# 44_pin_BB.net
KiCad netlist of a schematic drawn in EAGLE
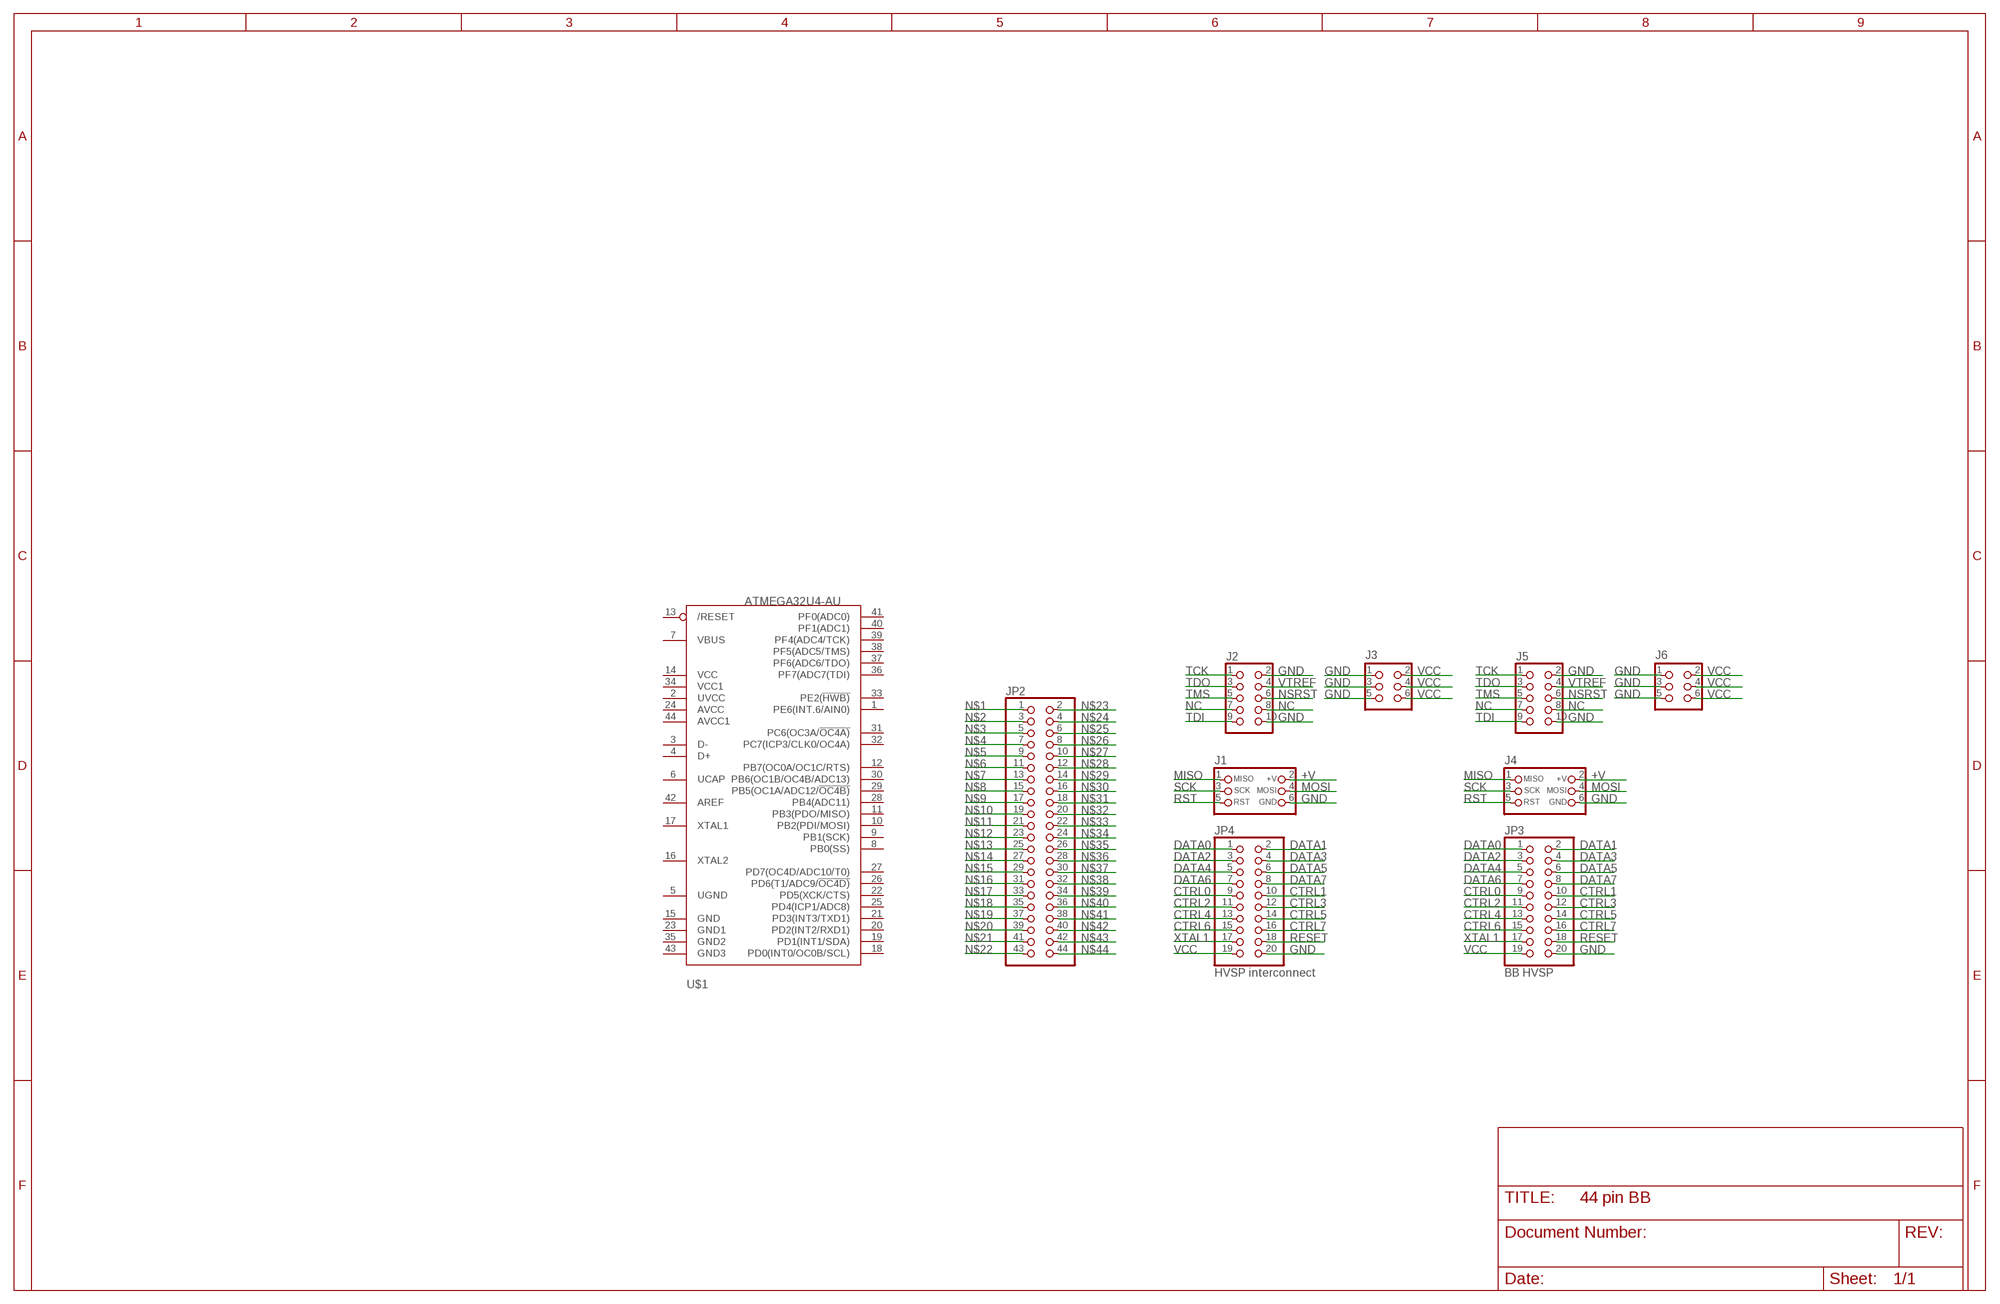
[diagram p0: schematic, sheet 1]

(export (version "E")
  (design (tool "Eeschema 10.0.6"))
  (components
    (comp (ref "J1")
      (value "CON_HEADER_PRG_AVR_ICSP")
      (footprint "eagle-import:HEADER_PRG_2X03")
      (libsource (lib "eagle-import") (part "CON_HEADER_PRG_AVR_ICSP"))
    )
    (comp (ref "J2")
      (value "CON_HEADER_2X05-PTH")
      (footprint "eagle-import:M2X5")
      (libsource (lib "eagle-import") (part "CON_HEADER_2X05-PTH"))
    )
    (comp (ref "J3")
      (value "CON_HEADER_2X03-PTH")
      (footprint "eagle-import:M2X3")
      (libsource (lib "eagle-import") (part "CON_HEADER_2X03-PTH"))
    )
    (comp (ref "J4")
      (value "CON_HEADER_PRG_AVR_ICSP")
      (footprint "eagle-import:HEADER_PRG_2X03")
      (libsource (lib "eagle-import") (part "CON_HEADER_PRG_AVR_ICSP"))
    )
    (comp (ref "J5")
      (value "CON_HEADER_2X05-PTH")
      (footprint "eagle-import:M2X5")
      (libsource (lib "eagle-import") (part "CON_HEADER_2X05-PTH"))
    )
    (comp (ref "J6")
      (value "CON_HEADER_2X03-PTH")
      (footprint "eagle-import:M2X3")
      (libsource (lib "eagle-import") (part "CON_HEADER_2X03-PTH"))
    )
    (comp (ref "JP2")
      (value "PINHD-2X22")
      (footprint "eagle-import:2X22")
      (libsource (lib "eagle-import") (part "PINHD-2X22"))
    )
    (comp (ref "JP3")
      (value "BB HVSP")
      (footprint "eagle-import:2X10")
      (libsource (lib "eagle-import") (part "PINHD-2X10"))
    )
    (comp (ref "JP4")
      (value "HVSP interconnect")
      (footprint "eagle-import:2X10")
      (libsource (lib "eagle-import") (part "PINHD-2X10"))
    )
    (comp (ref "U$1")
      (value "ATMEGA32U4-AU")
      (footprint "eagle-import:TQFP44")
      (libsource (lib "eagle-import") (part "ATMEGA32U4-AU"))
    )
  )
  (nets
    (net (code "1") (name "/+V") (class "Default")
      (node (ref "J1") (pin "2") (pinfunction "+V_2") (pintype "passive"))
      (node (ref "J4") (pin "2") (pinfunction "+V_2") (pintype "passive"))
    )
    (net (code "2") (name "/CTRL0") (class "Default")
      (node (ref "JP3") (pin "9") (pinfunction "9_9") (pintype "passive"))
      (node (ref "JP4") (pin "9") (pinfunction "9_9") (pintype "passive"))
    )
    (net (code "3") (name "/CTRL1") (class "Default")
      (node (ref "JP3") (pin "10") (pinfunction "10_10") (pintype "passive"))
      (node (ref "JP4") (pin "10") (pinfunction "10_10") (pintype "passive"))
    )
    (net (code "4") (name "/CTRL2") (class "Default")
      (node (ref "JP3") (pin "11") (pinfunction "11_11") (pintype "passive"))
      (node (ref "JP4") (pin "11") (pinfunction "11_11") (pintype "passive"))
    )
    (net (code "5") (name "/CTRL3") (class "Default")
      (node (ref "JP3") (pin "12") (pinfunction "12_12") (pintype "passive"))
      (node (ref "JP4") (pin "12") (pinfunction "12_12") (pintype "passive"))
    )
    (net (code "6") (name "/CTRL4") (class "Default")
      (node (ref "JP3") (pin "13") (pinfunction "13_13") (pintype "passive"))
      (node (ref "JP4") (pin "13") (pinfunction "13_13") (pintype "passive"))
    )
    (net (code "7") (name "/CTRL5") (class "Default")
      (node (ref "JP3") (pin "14") (pinfunction "14_14") (pintype "passive"))
      (node (ref "JP4") (pin "14") (pinfunction "14_14") (pintype "passive"))
    )
    (net (code "8") (name "/CTRL6") (class "Default")
      (node (ref "JP3") (pin "15") (pinfunction "15_15") (pintype "passive"))
      (node (ref "JP4") (pin "15") (pinfunction "15_15") (pintype "passive"))
    )
    (net (code "9") (name "/CTRL7") (class "Default")
      (node (ref "JP3") (pin "16") (pinfunction "16_16") (pintype "passive"))
      (node (ref "JP4") (pin "16") (pinfunction "16_16") (pintype "passive"))
    )
    (net (code "10") (name "/DATA0") (class "Default")
      (node (ref "JP3") (pin "1") (pinfunction "1_1") (pintype "passive"))
      (node (ref "JP4") (pin "1") (pinfunction "1_1") (pintype "passive"))
    )
    (net (code "11") (name "/DATA1") (class "Default")
      (node (ref "JP3") (pin "2") (pinfunction "2_2") (pintype "passive"))
      (node (ref "JP4") (pin "2") (pinfunction "2_2") (pintype "passive"))
    )
    (net (code "12") (name "/DATA2") (class "Default")
      (node (ref "JP3") (pin "3") (pinfunction "3_3") (pintype "passive"))
      (node (ref "JP4") (pin "3") (pinfunction "3_3") (pintype "passive"))
    )
    (net (code "13") (name "/DATA3") (class "Default")
      (node (ref "JP3") (pin "4") (pinfunction "4_4") (pintype "passive"))
      (node (ref "JP4") (pin "4") (pinfunction "4_4") (pintype "passive"))
    )
    (net (code "14") (name "/DATA4") (class "Default")
      (node (ref "JP3") (pin "5") (pinfunction "5_5") (pintype "passive"))
      (node (ref "JP4") (pin "5") (pinfunction "5_5") (pintype "passive"))
    )
    (net (code "15") (name "/DATA5") (class "Default")
      (node (ref "JP3") (pin "6") (pinfunction "6_6") (pintype "passive"))
      (node (ref "JP4") (pin "6") (pinfunction "6_6") (pintype "passive"))
    )
    (net (code "16") (name "/DATA6") (class "Default")
      (node (ref "JP3") (pin "7") (pinfunction "7_7") (pintype "passive"))
      (node (ref "JP4") (pin "7") (pinfunction "7_7") (pintype "passive"))
    )
    (net (code "17") (name "/DATA7") (class "Default")
      (node (ref "JP3") (pin "8") (pinfunction "8_8") (pintype "passive"))
      (node (ref "JP4") (pin "8") (pinfunction "8_8") (pintype "passive"))
    )
    (net (code "18") (name "/GND") (class "Default")
      (node (ref "J1") (pin "6") (pinfunction "GND_6") (pintype "passive"))
      (node (ref "J2") (pin "10") (pinfunction "10_10") (pintype "passive"))
      (node (ref "J2") (pin "2") (pinfunction "2_2") (pintype "passive"))
      (node (ref "J3") (pin "1") (pinfunction "1_1") (pintype "passive"))
      (node (ref "J3") (pin "3") (pinfunction "3_3") (pintype "passive"))
      (node (ref "J3") (pin "5") (pinfunction "5_5") (pintype "passive"))
      (node (ref "J4") (pin "6") (pinfunction "GND_6") (pintype "passive"))
      (node (ref "J5") (pin "10") (pinfunction "10_10") (pintype "passive"))
      (node (ref "J5") (pin "2") (pinfunction "2_2") (pintype "passive"))
      (node (ref "J6") (pin "1") (pinfunction "1_1") (pintype "passive"))
      (node (ref "J6") (pin "3") (pinfunction "3_3") (pintype "passive"))
      (node (ref "J6") (pin "5") (pinfunction "5_5") (pintype "passive"))
      (node (ref "JP3") (pin "20") (pinfunction "20_20") (pintype "passive"))
      (node (ref "JP4") (pin "20") (pinfunction "20_20") (pintype "passive"))
    )
    (net (code "19") (name "/MISO") (class "Default")
      (node (ref "J1") (pin "1") (pinfunction "MISO_1") (pintype "passive"))
      (node (ref "J4") (pin "1") (pinfunction "MISO_1") (pintype "passive"))
    )
    (net (code "20") (name "/MOSI") (class "Default")
      (node (ref "J1") (pin "4") (pinfunction "MOSI_4") (pintype "passive"))
      (node (ref "J4") (pin "4") (pinfunction "MOSI_4") (pintype "passive"))
    )
    (net (code "21") (name "/N$1") (class "Default")
      (node (ref "JP2") (pin "1") (pinfunction "1_1") (pintype "passive"))
    )
    (net (code "22") (name "/N$2") (class "Default")
      (node (ref "JP2") (pin "3") (pinfunction "3_3") (pintype "passive"))
    )
    (net (code "23") (name "/N$3") (class "Default")
      (node (ref "JP2") (pin "5") (pinfunction "5_5") (pintype "passive"))
    )
    (net (code "24") (name "/N$4") (class "Default")
      (node (ref "JP2") (pin "7") (pinfunction "7_7") (pintype "passive"))
    )
    (net (code "25") (name "/N$5") (class "Default")
      (node (ref "JP2") (pin "9") (pinfunction "9_9") (pintype "passive"))
    )
    (net (code "26") (name "/N$6") (class "Default")
      (node (ref "JP2") (pin "11") (pinfunction "11_11") (pintype "passive"))
    )
    (net (code "27") (name "/N$7") (class "Default")
      (node (ref "JP2") (pin "13") (pinfunction "13_13") (pintype "passive"))
    )
    (net (code "28") (name "/N$8") (class "Default")
      (node (ref "JP2") (pin "15") (pinfunction "15_15") (pintype "passive"))
    )
    (net (code "29") (name "/N$9") (class "Default")
      (node (ref "JP2") (pin "17") (pinfunction "17_17") (pintype "passive"))
    )
    (net (code "30") (name "/N$10") (class "Default")
      (node (ref "JP2") (pin "19") (pinfunction "19_19") (pintype "passive"))
    )
    (net (code "31") (name "/N$11") (class "Default")
      (node (ref "JP2") (pin "21") (pinfunction "21_21") (pintype "passive"))
    )
    (net (code "32") (name "/N$12") (class "Default")
      (node (ref "JP2") (pin "23") (pinfunction "23_23") (pintype "passive"))
    )
    (net (code "33") (name "/N$13") (class "Default")
      (node (ref "JP2") (pin "25") (pinfunction "25_25") (pintype "passive"))
    )
    (net (code "34") (name "/N$14") (class "Default")
      (node (ref "JP2") (pin "27") (pinfunction "27_27") (pintype "passive"))
    )
    (net (code "35") (name "/N$15") (class "Default")
      (node (ref "JP2") (pin "29") (pinfunction "29_29") (pintype "passive"))
    )
    (net (code "36") (name "/N$16") (class "Default")
      (node (ref "JP2") (pin "31") (pinfunction "31_31") (pintype "passive"))
    )
    (net (code "37") (name "/N$17") (class "Default")
      (node (ref "JP2") (pin "33") (pinfunction "33_33") (pintype "passive"))
    )
    (net (code "38") (name "/N$18") (class "Default")
      (node (ref "JP2") (pin "35") (pinfunction "35_35") (pintype "passive"))
    )
    (net (code "39") (name "/N$19") (class "Default")
      (node (ref "JP2") (pin "37") (pinfunction "37_37") (pintype "passive"))
    )
    (net (code "40") (name "/N$20") (class "Default")
      (node (ref "JP2") (pin "39") (pinfunction "39_39") (pintype "passive"))
    )
    (net (code "41") (name "/N$21") (class "Default")
      (node (ref "JP2") (pin "41") (pinfunction "41_41") (pintype "passive"))
    )
    (net (code "42") (name "/N$22") (class "Default")
      (node (ref "JP2") (pin "43") (pinfunction "43_43") (pintype "passive"))
    )
    (net (code "43") (name "/N$23") (class "Default")
      (node (ref "JP2") (pin "2") (pinfunction "2_2") (pintype "passive"))
    )
    (net (code "44") (name "/N$24") (class "Default")
      (node (ref "JP2") (pin "4") (pinfunction "4_4") (pintype "passive"))
    )
    (net (code "45") (name "/N$25") (class "Default")
      (node (ref "JP2") (pin "6") (pinfunction "6_6") (pintype "passive"))
    )
    (net (code "46") (name "/N$26") (class "Default")
      (node (ref "JP2") (pin "8") (pinfunction "8_8") (pintype "passive"))
    )
    (net (code "47") (name "/N$27") (class "Default")
      (node (ref "JP2") (pin "10") (pinfunction "10_10") (pintype "passive"))
    )
    (net (code "48") (name "/N$28") (class "Default")
      (node (ref "JP2") (pin "12") (pinfunction "12_12") (pintype "passive"))
    )
    (net (code "49") (name "/N$29") (class "Default")
      (node (ref "JP2") (pin "14") (pinfunction "14_14") (pintype "passive"))
    )
    (net (code "50") (name "/N$30") (class "Default")
      (node (ref "JP2") (pin "16") (pinfunction "16_16") (pintype "passive"))
    )
    (net (code "51") (name "/N$31") (class "Default")
      (node (ref "JP2") (pin "18") (pinfunction "18_18") (pintype "passive"))
    )
    (net (code "52") (name "/N$32") (class "Default")
      (node (ref "JP2") (pin "20") (pinfunction "20_20") (pintype "passive"))
    )
    (net (code "53") (name "/N$33") (class "Default")
      (node (ref "JP2") (pin "22") (pinfunction "22_22") (pintype "passive"))
    )
    (net (code "54") (name "/N$34") (class "Default")
      (node (ref "JP2") (pin "24") (pinfunction "24_24") (pintype "passive"))
    )
    (net (code "55") (name "/N$35") (class "Default")
      (node (ref "JP2") (pin "26") (pinfunction "26_26") (pintype "passive"))
    )
    (net (code "56") (name "/N$36") (class "Default")
      (node (ref "JP2") (pin "28") (pinfunction "28_28") (pintype "passive"))
    )
    (net (code "57") (name "/N$37") (class "Default")
      (node (ref "JP2") (pin "30") (pinfunction "30_30") (pintype "passive"))
    )
    (net (code "58") (name "/N$38") (class "Default")
      (node (ref "JP2") (pin "32") (pinfunction "32_32") (pintype "passive"))
    )
    (net (code "59") (name "/N$39") (class "Default")
      (node (ref "JP2") (pin "34") (pinfunction "34_34") (pintype "passive"))
    )
    (net (code "60") (name "/N$40") (class "Default")
      (node (ref "JP2") (pin "36") (pinfunction "36_36") (pintype "passive"))
    )
    (net (code "61") (name "/N$41") (class "Default")
      (node (ref "JP2") (pin "38") (pinfunction "38_38") (pintype "passive"))
    )
    (net (code "62") (name "/N$42") (class "Default")
      (node (ref "JP2") (pin "40") (pinfunction "40_40") (pintype "passive"))
    )
    (net (code "63") (name "/N$43") (class "Default")
      (node (ref "JP2") (pin "42") (pinfunction "42_42") (pintype "passive"))
    )
    (net (code "64") (name "/N$44") (class "Default")
      (node (ref "JP2") (pin "44") (pinfunction "44_44") (pintype "passive"))
    )
    (net (code "65") (name "/NC") (class "Default")
      (node (ref "J2") (pin "7") (pinfunction "7_7") (pintype "passive"))
      (node (ref "J2") (pin "8") (pinfunction "8_8") (pintype "passive"))
      (node (ref "J5") (pin "7") (pinfunction "7_7") (pintype "passive"))
      (node (ref "J5") (pin "8") (pinfunction "8_8") (pintype "passive"))
    )
    (net (code "66") (name "/NSRST") (class "Default")
      (node (ref "J2") (pin "6") (pinfunction "6_6") (pintype "passive"))
      (node (ref "J5") (pin "6") (pinfunction "6_6") (pintype "passive"))
    )
    (net (code "67") (name "/RESET") (class "Default")
      (node (ref "JP3") (pin "18") (pinfunction "18_18") (pintype "passive"))
      (node (ref "JP4") (pin "18") (pinfunction "18_18") (pintype "passive"))
    )
    (net (code "68") (name "/RST") (class "Default")
      (node (ref "J1") (pin "5") (pinfunction "RST_5") (pintype "passive"))
      (node (ref "J4") (pin "5") (pinfunction "RST_5") (pintype "passive"))
    )
    (net (code "69") (name "/SCK") (class "Default")
      (node (ref "J1") (pin "3") (pinfunction "SCK_3") (pintype "passive"))
      (node (ref "J4") (pin "3") (pinfunction "SCK_3") (pintype "passive"))
    )
    (net (code "70") (name "/TCK") (class "Default")
      (node (ref "J2") (pin "1") (pinfunction "1_1") (pintype "passive"))
      (node (ref "J5") (pin "1") (pinfunction "1_1") (pintype "passive"))
    )
    (net (code "71") (name "/TDI") (class "Default")
      (node (ref "J2") (pin "9") (pinfunction "9_9") (pintype "passive"))
      (node (ref "J5") (pin "9") (pinfunction "9_9") (pintype "passive"))
    )
    (net (code "72") (name "/TDO") (class "Default")
      (node (ref "J2") (pin "3") (pinfunction "3_3") (pintype "passive"))
      (node (ref "J5") (pin "3") (pinfunction "3_3") (pintype "passive"))
    )
    (net (code "73") (name "/TMS") (class "Default")
      (node (ref "J2") (pin "5") (pinfunction "5_5") (pintype "passive"))
      (node (ref "J5") (pin "5") (pinfunction "5_5") (pintype "passive"))
    )
    (net (code "74") (name "/VCC") (class "Default")
      (node (ref "J3") (pin "2") (pinfunction "2_2") (pintype "passive"))
      (node (ref "J3") (pin "4") (pinfunction "4_4") (pintype "passive"))
      (node (ref "J3") (pin "6") (pinfunction "6_6") (pintype "passive"))
      (node (ref "J6") (pin "2") (pinfunction "2_2") (pintype "passive"))
      (node (ref "J6") (pin "4") (pinfunction "4_4") (pintype "passive"))
      (node (ref "J6") (pin "6") (pinfunction "6_6") (pintype "passive"))
      (node (ref "JP3") (pin "19") (pinfunction "19_19") (pintype "passive"))
      (node (ref "JP4") (pin "19") (pinfunction "19_19") (pintype "passive"))
    )
    (net (code "75") (name "/VTREF") (class "Default")
      (node (ref "J2") (pin "4") (pinfunction "4_4") (pintype "passive"))
      (node (ref "J5") (pin "4") (pinfunction "4_4") (pintype "passive"))
    )
    (net (code "76") (name "/XTAL1") (class "Default")
      (node (ref "JP3") (pin "17") (pinfunction "17_17") (pintype "passive"))
      (node (ref "JP4") (pin "17") (pinfunction "17_17") (pintype "passive"))
    )
    (net (code "77") (name "unconnected-(U$1-AREF-Pad42)") (class "Default")
      (node (ref "U$1") (pin "42") (pinfunction "AREF_42") (pintype "bidirectional"))
    )
    (net (code "78") (name "unconnected-(U$1-AVCC-Pad24)") (class "Default")
      (node (ref "U$1") (pin "24") (pinfunction "AVCC_24") (pintype "bidirectional"))
    )
    (net (code "79") (name "unconnected-(U$1-AVCC1-Pad44)") (class "Default")
      (node (ref "U$1") (pin "44") (pinfunction "AVCC1_44") (pintype "bidirectional"))
    )
    (net (code "80") (name "unconnected-(U$1-D+-Pad4)") (class "Default")
      (node (ref "U$1") (pin "4") (pinfunction "D+_4") (pintype "bidirectional"))
    )
    (net (code "81") (name "unconnected-(U$1-D--Pad3)") (class "Default")
      (node (ref "U$1") (pin "3") (pinfunction "D-_3") (pintype "bidirectional"))
    )
    (net (code "82") (name "unconnected-(U$1-GND-Pad15)") (class "Default")
      (node (ref "U$1") (pin "15") (pinfunction "GND_15") (pintype "bidirectional"))
    )
    (net (code "83") (name "unconnected-(U$1-GND1-Pad23)") (class "Default")
      (node (ref "U$1") (pin "23") (pinfunction "GND1_23") (pintype "bidirectional"))
    )
    (net (code "84") (name "unconnected-(U$1-GND2-Pad35)") (class "Default")
      (node (ref "U$1") (pin "35") (pinfunction "GND2_35") (pintype "bidirectional"))
    )
    (net (code "85") (name "unconnected-(U$1-GND3-Pad43)") (class "Default")
      (node (ref "U$1") (pin "43") (pinfunction "GND3_43") (pintype "bidirectional"))
    )
    (net (code "86") (name "unconnected-(U$1-PB0(SS)-Pad8)") (class "Default")
      (node (ref "U$1") (pin "8") (pinfunction "PB0(SS)_8") (pintype "bidirectional"))
    )
    (net (code "87") (name "unconnected-(U$1-PB1(SCK)-Pad9)") (class "Default")
      (node (ref "U$1") (pin "9") (pinfunction "PB1(SCK)_9") (pintype "bidirectional"))
    )
    (net (code "88") (name "unconnected-(U$1-PB2(PDI{slash}MOSI)-Pad10)") (class "Default")
      (node (ref "U$1") (pin "10") (pinfunction "PB2(PDI/MOSI)_10") (pintype "bidirectional"))
    )
    (net (code "89") (name "unconnected-(U$1-PB3(PDO{slash}MISO)-Pad11)") (class "Default")
      (node (ref "U$1") (pin "11") (pinfunction "PB3(PDO/MISO)_11") (pintype "bidirectional"))
    )
    (net (code "90") (name "unconnected-(U$1-PB4(ADC11)-Pad28)") (class "Default")
      (node (ref "U$1") (pin "28") (pinfunction "PB4(ADC11)_28") (pintype "bidirectional"))
    )
    (net (code "91") (name "unconnected-(U$1-PB5(OC1A{slash}ADC12{slash}~{OC4B})-Pad29)") (class "Default")
      (node (ref "U$1") (pin "29") (pinfunction "PB5(OC1A/ADC12/~{OC4B})_29") (pintype "bidirectional"))
    )
    (net (code "92") (name "unconnected-(U$1-PB6(OC1B{slash}OC4B{slash}ADC13)-Pad30)") (class "Default")
      (node (ref "U$1") (pin "30") (pinfunction "PB6(OC1B/OC4B/ADC13)_30") (pintype "bidirectional"))
    )
    (net (code "93") (name "unconnected-(U$1-PB7(OC0A{slash}OC1C{slash}RTS)-Pad12)") (class "Default")
      (node (ref "U$1") (pin "12") (pinfunction "PB7(OC0A/OC1C/RTS)_12") (pintype "bidirectional"))
    )
    (net (code "94") (name "unconnected-(U$1-PC6(OC3A{slash}~{OC4A})-Pad31)") (class "Default")
      (node (ref "U$1") (pin "31") (pinfunction "PC6(OC3A/~{OC4A})_31") (pintype "bidirectional"))
    )
    (net (code "95") (name "unconnected-(U$1-PC7(ICP3{slash}CLK0{slash}OC4A)-Pad32)") (class "Default")
      (node (ref "U$1") (pin "32") (pinfunction "PC7(ICP3/CLK0/OC4A)_32") (pintype "bidirectional"))
    )
    (net (code "96") (name "unconnected-(U$1-PD0(INT0{slash}OC0B{slash}SCL)-Pad18)") (class "Default")
      (node (ref "U$1") (pin "18") (pinfunction "PD0(INT0/OC0B/SCL)_18") (pintype "bidirectional"))
    )
    (net (code "97") (name "unconnected-(U$1-PD1(INT1{slash}SDA)-Pad19)") (class "Default")
      (node (ref "U$1") (pin "19") (pinfunction "PD1(INT1/SDA)_19") (pintype "bidirectional"))
    )
    (net (code "98") (name "unconnected-(U$1-PD2(INT2{slash}RXD1)-Pad20)") (class "Default")
      (node (ref "U$1") (pin "20") (pinfunction "PD2(INT2/RXD1)_20") (pintype "bidirectional"))
    )
    (net (code "99") (name "unconnected-(U$1-PD3(INT3{slash}TXD1)-Pad21)") (class "Default")
      (node (ref "U$1") (pin "21") (pinfunction "PD3(INT3/TXD1)_21") (pintype "bidirectional"))
    )
    (net (code "100") (name "unconnected-(U$1-PD4(ICP1{slash}ADC8)-Pad25)") (class "Default")
      (node (ref "U$1") (pin "25") (pinfunction "PD4(ICP1/ADC8)_25") (pintype "bidirectional"))
    )
    (net (code "101") (name "unconnected-(U$1-PD5(XCK{slash}CTS)-Pad22)") (class "Default")
      (node (ref "U$1") (pin "22") (pinfunction "PD5(XCK/CTS)_22") (pintype "bidirectional"))
    )
    (net (code "102") (name "unconnected-(U$1-PD6(T1{slash}ADC9{slash}~{OC4D})-Pad26)") (class "Default")
      (node (ref "U$1") (pin "26") (pinfunction "PD6(T1/ADC9/~{OC4D})_26") (pintype "bidirectional"))
    )
    (net (code "103") (name "unconnected-(U$1-PD7(OC4D{slash}ADC10{slash}T0)-Pad27)") (class "Default")
      (node (ref "U$1") (pin "27") (pinfunction "PD7(OC4D/ADC10/T0)_27") (pintype "bidirectional"))
    )
    (net (code "104") (name "unconnected-(U$1-PE2(~{HWB})-Pad33)") (class "Default")
      (node (ref "U$1") (pin "33") (pinfunction "PE2(~{HWB})_33") (pintype "bidirectional"))
    )
    (net (code "105") (name "unconnected-(U$1-PE6(INT.6{slash}AIN0)-Pad1)") (class "Default")
      (node (ref "U$1") (pin "1") (pinfunction "PE6(INT.6/AIN0)_1") (pintype "bidirectional"))
    )
    (net (code "106") (name "unconnected-(U$1-PF0(ADC0)-Pad41)") (class "Default")
      (node (ref "U$1") (pin "41") (pinfunction "PF0(ADC0)_41") (pintype "bidirectional"))
    )
    (net (code "107") (name "unconnected-(U$1-PF1(ADC1)-Pad40)") (class "Default")
      (node (ref "U$1") (pin "40") (pinfunction "PF1(ADC1)_40") (pintype "bidirectional"))
    )
    (net (code "108") (name "unconnected-(U$1-PF4(ADC4{slash}TCK)-Pad39)") (class "Default")
      (node (ref "U$1") (pin "39") (pinfunction "PF4(ADC4/TCK)_39") (pintype "bidirectional"))
    )
    (net (code "109") (name "unconnected-(U$1-PF5(ADC5{slash}TMS)-Pad38)") (class "Default")
      (node (ref "U$1") (pin "38") (pinfunction "PF5(ADC5/TMS)_38") (pintype "bidirectional"))
    )
    (net (code "110") (name "unconnected-(U$1-PF6(ADC6{slash}TDO)-Pad37)") (class "Default")
      (node (ref "U$1") (pin "37") (pinfunction "PF6(ADC6/TDO)_37") (pintype "bidirectional"))
    )
    (net (code "111") (name "unconnected-(U$1-PF7(ADC7(TDI)-Pad36)") (class "Default")
      (node (ref "U$1") (pin "36") (pinfunction "PF7(ADC7(TDI)_36") (pintype "bidirectional"))
    )
    (net (code "112") (name "unconnected-(U$1-UCAP-Pad6)") (class "Default")
      (node (ref "U$1") (pin "6") (pinfunction "UCAP_6") (pintype "bidirectional"))
    )
    (net (code "113") (name "unconnected-(U$1-UGND-Pad5)") (class "Default")
      (node (ref "U$1") (pin "5") (pinfunction "UGND_5") (pintype "bidirectional"))
    )
    (net (code "114") (name "unconnected-(U$1-UVCC-Pad2)") (class "Default")
      (node (ref "U$1") (pin "2") (pinfunction "UVCC_2") (pintype "bidirectional"))
    )
    (net (code "115") (name "unconnected-(U$1-VBUS-Pad7)") (class "Default")
      (node (ref "U$1") (pin "7") (pinfunction "VBUS_7") (pintype "bidirectional"))
    )
    (net (code "116") (name "unconnected-(U$1-VCC-Pad14)") (class "Default")
      (node (ref "U$1") (pin "14") (pinfunction "VCC_14") (pintype "bidirectional"))
    )
    (net (code "117") (name "unconnected-(U$1-VCC1-Pad34)") (class "Default")
      (node (ref "U$1") (pin "34") (pinfunction "VCC1_34") (pintype "bidirectional"))
    )
    (net (code "118") (name "unconnected-(U$1-XTAL1-Pad17)") (class "Default")
      (node (ref "U$1") (pin "17") (pinfunction "XTAL1_17") (pintype "bidirectional"))
    )
    (net (code "119") (name "unconnected-(U$1-XTAL2-Pad16)") (class "Default")
      (node (ref "U$1") (pin "16") (pinfunction "XTAL2_16") (pintype "bidirectional"))
    )
    (net (code "120") (name "unconnected-(U$1-{slash}RESET-Pad13)") (class "Default")
      (node (ref "U$1") (pin "13") (pinfunction "/RESET_13") (pintype "bidirectional"))
    )
  )
)
